# lv_io_lim.net
KiCad netlist of a schematic drawn in Altium Designer
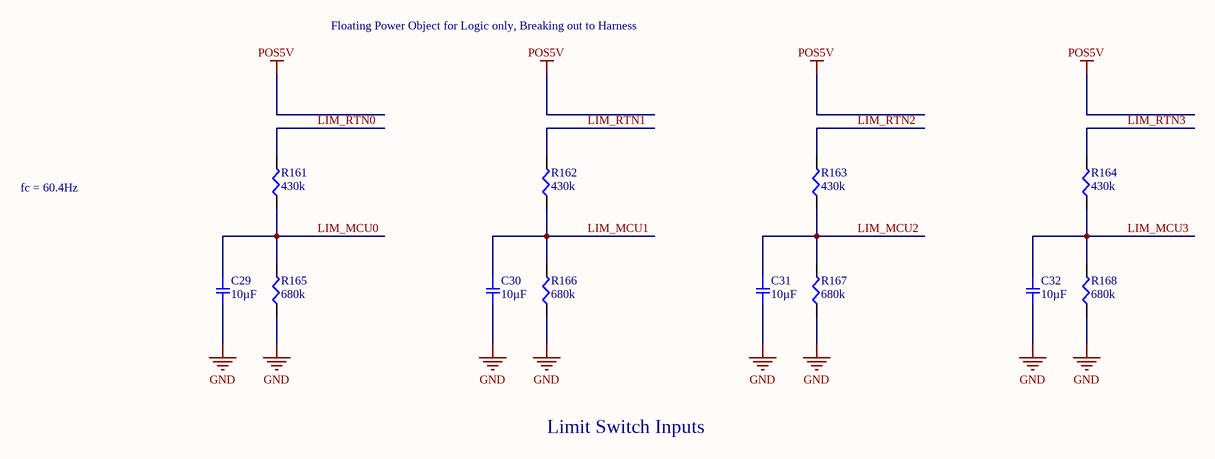
[diagram p0: lv_io_lim.SchDoc]

(export (version "E")
  (design (tool "Eeschema 10.0.6"))
  (components
    (comp (ref "C29")
      (value "10µF")
      (footprint "SMD-0805C")
      (description "CAP CER 10UF 25V X6S 0805")
      (fields
        (field (name "DIGI-KEY PART NUMBER") "490-10502-1-ND")
        (field (name "PART NUMBER") "GRM21BC81E106KE51L")
      )
      (libsource (lib "capacitor") (part "GRM21BC81E106KE51L"))
    )
    (comp (ref "C30")
      (value "10µF")
      (footprint "SMD-0805C")
      (description "CAP CER 10UF 25V X6S 0805")
      (fields
        (field (name "DIGI-KEY PART NUMBER") "490-10502-1-ND")
        (field (name "PART NUMBER") "GRM21BC81E106KE51L")
      )
      (libsource (lib "capacitor") (part "GRM21BC81E106KE51L"))
    )
    (comp (ref "C31")
      (value "10µF")
      (footprint "SMD-0805C")
      (description "CAP CER 10UF 25V X6S 0805")
      (fields
        (field (name "DIGI-KEY PART NUMBER") "490-10502-1-ND")
        (field (name "PART NUMBER") "GRM21BC81E106KE51L")
      )
      (libsource (lib "capacitor") (part "GRM21BC81E106KE51L"))
    )
    (comp (ref "C32")
      (value "10µF")
      (footprint "SMD-0805C")
      (description "CAP CER 10UF 25V X6S 0805")
      (fields
        (field (name "DIGI-KEY PART NUMBER") "490-10502-1-ND")
        (field (name "PART NUMBER") "GRM21BC81E106KE51L")
      )
      (libsource (lib "capacitor") (part "GRM21BC81E106KE51L"))
    )
    (comp (ref "R161")
      (value "430k")
      (footprint "SMD-0402-RES")
      (description "RES SMD 430K OHM 5% 1/10W 0402")
      (fields (field (name "PART NUMBER") "ERJ-2GEJ434X") (field (name "DIGI-KEY PART NUMBER") "P430KJCT-ND"))
      (libsource (lib "resistor") (part "ERJ-2GEJ434X"))
    )
    (comp (ref "R162")
      (value "430k")
      (footprint "SMD-0402-RES")
      (description "RES SMD 430K OHM 5% 1/10W 0402")
      (fields (field (name "PART NUMBER") "ERJ-2GEJ434X") (field (name "DIGI-KEY PART NUMBER") "P430KJCT-ND"))
      (libsource (lib "resistor") (part "ERJ-2GEJ434X"))
    )
    (comp (ref "R163")
      (value "430k")
      (footprint "SMD-0402-RES")
      (description "RES SMD 430K OHM 5% 1/10W 0402")
      (fields (field (name "PART NUMBER") "ERJ-2GEJ434X") (field (name "DIGI-KEY PART NUMBER") "P430KJCT-ND"))
      (libsource (lib "resistor") (part "ERJ-2GEJ434X"))
    )
    (comp (ref "R164")
      (value "430k")
      (footprint "SMD-0402-RES")
      (description "RES SMD 430K OHM 5% 1/10W 0402")
      (fields (field (name "PART NUMBER") "ERJ-2GEJ434X") (field (name "DIGI-KEY PART NUMBER") "P430KJCT-ND"))
      (libsource (lib "resistor") (part "ERJ-2GEJ434X"))
    )
    (comp (ref "R165")
      (value "680k")
      (footprint "SMD-0402-RES")
      (description "RES SMD 680K OHM 5% 1/10W 0402")
      (fields (field (name "PART NUMBER") "ERJ-2GEJ684X") (field (name "DIGI-KEY PART NUMBER") "P680KJCT-ND"))
      (libsource (lib "resistor") (part "ERJ-2GEJ684X"))
    )
    (comp (ref "R166")
      (value "680k")
      (footprint "SMD-0402-RES")
      (description "RES SMD 680K OHM 5% 1/10W 0402")
      (fields (field (name "PART NUMBER") "ERJ-2GEJ684X") (field (name "DIGI-KEY PART NUMBER") "P680KJCT-ND"))
      (libsource (lib "resistor") (part "ERJ-2GEJ684X"))
    )
    (comp (ref "R167")
      (value "680k")
      (footprint "SMD-0402-RES")
      (description "RES SMD 680K OHM 5% 1/10W 0402")
      (fields (field (name "PART NUMBER") "ERJ-2GEJ684X") (field (name "DIGI-KEY PART NUMBER") "P680KJCT-ND"))
      (libsource (lib "resistor") (part "ERJ-2GEJ684X"))
    )
    (comp (ref "R168")
      (value "680k")
      (footprint "SMD-0402-RES")
      (description "RES SMD 680K OHM 5% 1/10W 0402")
      (fields (field (name "PART NUMBER") "ERJ-2GEJ684X") (field (name "DIGI-KEY PART NUMBER") "P680KJCT-ND"))
      (libsource (lib "resistor") (part "ERJ-2GEJ684X"))
    )
  )
  (nets
    (net (code "1") (name "/LIM_MCU0") (class "Default")
      (node (ref "C29") (pin "1") (pinfunction "1_1") (pintype "passive"))
      (node (ref "R161") (pin "1") (pinfunction "1_1") (pintype "passive"))
      (node (ref "R165") (pin "2") (pinfunction "2_2") (pintype "passive"))
    )
    (net (code "2") (name "/LIM_MCU1") (class "Default")
      (node (ref "C30") (pin "1") (pinfunction "1_1") (pintype "passive"))
      (node (ref "R162") (pin "1") (pinfunction "1_1") (pintype "passive"))
      (node (ref "R166") (pin "2") (pinfunction "2_2") (pintype "passive"))
    )
    (net (code "3") (name "/LIM_MCU2") (class "Default")
      (node (ref "C31") (pin "1") (pinfunction "1_1") (pintype "passive"))
      (node (ref "R163") (pin "1") (pinfunction "1_1") (pintype "passive"))
      (node (ref "R167") (pin "2") (pinfunction "2_2") (pintype "passive"))
    )
    (net (code "4") (name "/LIM_MCU3") (class "Default")
      (node (ref "C32") (pin "1") (pinfunction "1_1") (pintype "passive"))
      (node (ref "R164") (pin "1") (pinfunction "1_1") (pintype "passive"))
      (node (ref "R168") (pin "2") (pinfunction "2_2") (pintype "passive"))
    )
    (net (code "5") (name "/LIM_RTN0") (class "Default")
      (node (ref "R161") (pin "2") (pinfunction "2_2") (pintype "passive"))
    )
    (net (code "6") (name "/LIM_RTN1") (class "Default")
      (node (ref "R162") (pin "2") (pinfunction "2_2") (pintype "passive"))
    )
    (net (code "7") (name "/LIM_RTN2") (class "Default")
      (node (ref "R163") (pin "2") (pinfunction "2_2") (pintype "passive"))
    )
    (net (code "8") (name "/LIM_RTN3") (class "Default")
      (node (ref "R164") (pin "2") (pinfunction "2_2") (pintype "passive"))
    )
    (net (code "9") (name "GND") (class "Default")
      (node (ref "C29") (pin "2") (pinfunction "2_2") (pintype "passive"))
      (node (ref "C30") (pin "2") (pinfunction "2_2") (pintype "passive"))
      (node (ref "C31") (pin "2") (pinfunction "2_2") (pintype "passive"))
      (node (ref "C32") (pin "2") (pinfunction "2_2") (pintype "passive"))
      (node (ref "R165") (pin "1") (pinfunction "1_1") (pintype "passive"))
      (node (ref "R166") (pin "1") (pinfunction "1_1") (pintype "passive"))
      (node (ref "R167") (pin "1") (pinfunction "1_1") (pintype "passive"))
      (node (ref "R168") (pin "1") (pinfunction "1_1") (pintype "passive"))
    )
  )
)
